# Teensy_Interface.net
KiCad netlist of a schematic drawn in Altium Designer
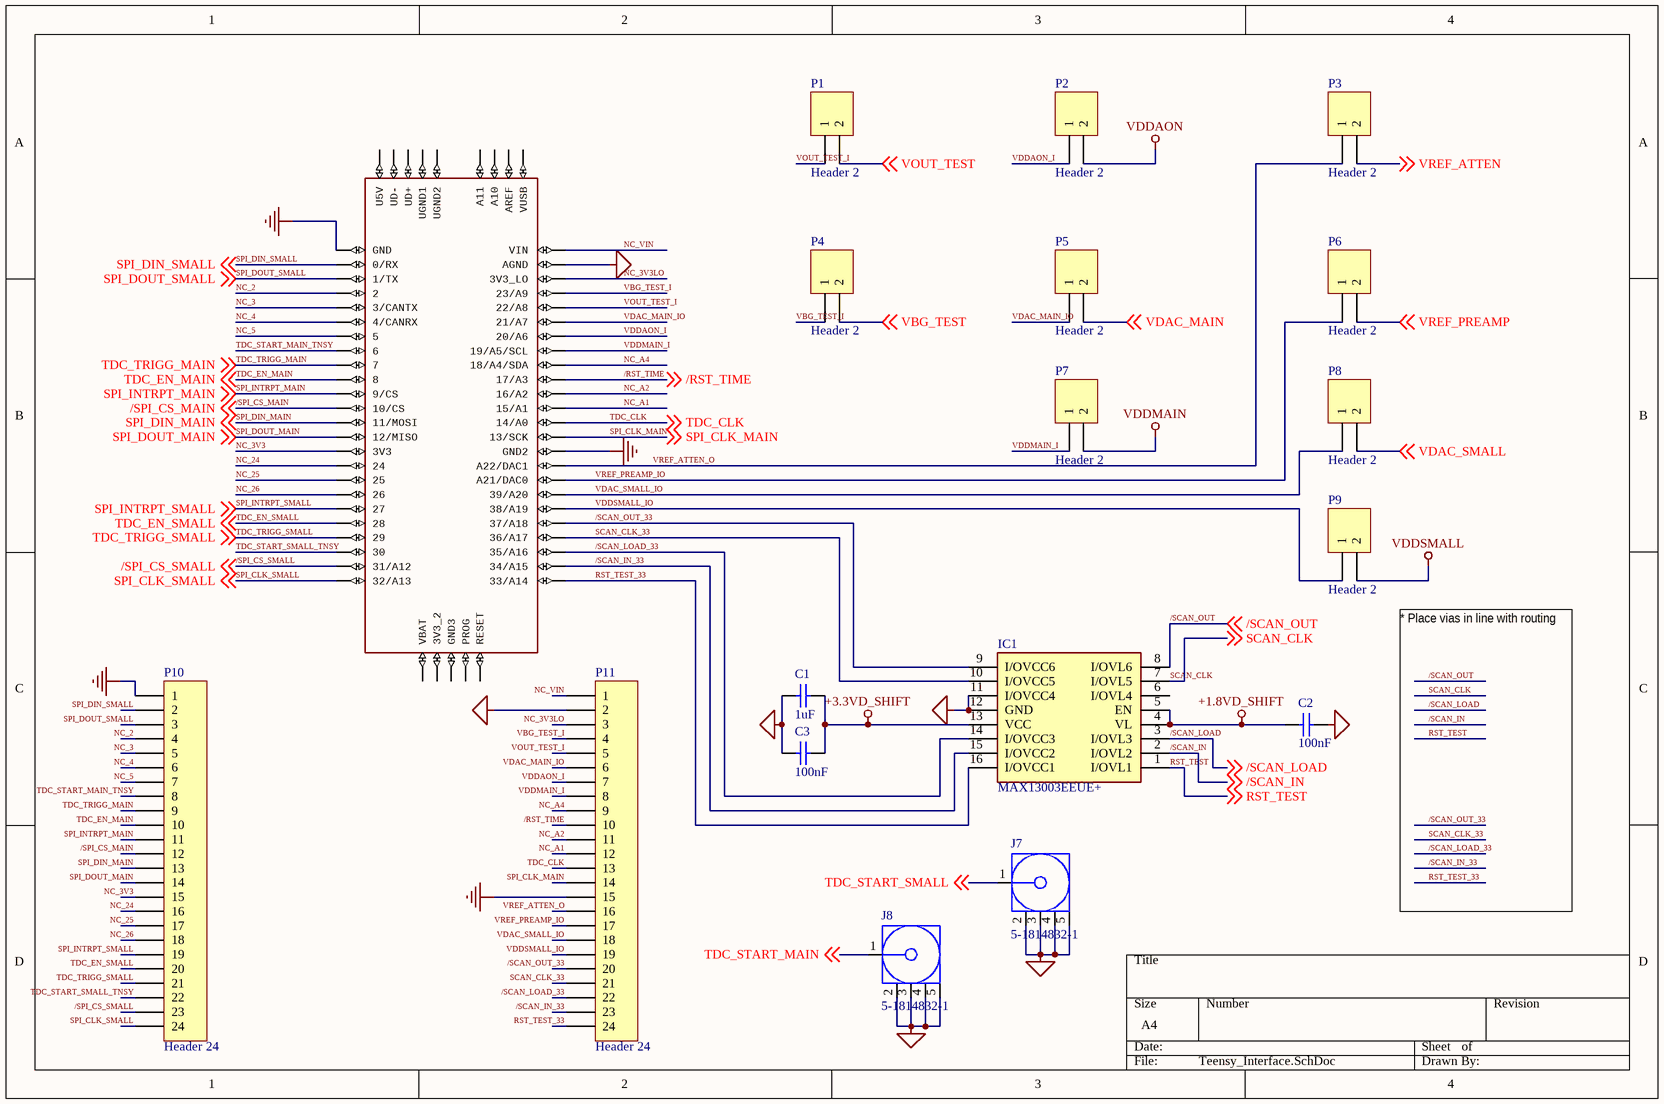
[diagram p0: Teensy_Interface.SchDoc]

(export (version "E")
  (design (tool "Eeschema 10.0.6"))
  (components
    (comp (ref "C1")
      (value "1uF")
      (footprint "CAPC1608X90X35ML10T15")
      (description "0603")
      (fields (field (name "MANUFACTURER") "Murata"))
      (libsource (lib "Altium Content Vault") (part "CAP-NP-2"))
    )
    (comp (ref "C2")
      (value "100nF")
      (footprint "CAPC1608X90X35ML10T15")
      (description "0603")
      (fields (field (name "MANUFACTURER") "Murata"))
      (libsource (lib "Altium Content Vault") (part "CAP-NP-2"))
    )
    (comp (ref "C3")
      (value "100nF")
      (footprint "CAPC1608X90X35ML10T15")
      (description "0603")
      (fields (field (name "MANUFACTURER") "Murata"))
      (libsource (lib "Altium Content Vault") (part "CAP-NP-2"))
    )
    (comp (ref "IC1")
      (value "MAX13003EEUE+")
      (footprint "SamacSys:SOP65P640X110-16N")
      (description "Integrated Circuit")
      (libsource (lib "*") (part "MAX13003EEUE+"))
    )
    (comp (ref "J7")
      (value "5-1814832-1")
      (footprint "TECO-5-1814832-1_V")
      (fields (field (name "MANUFACTURER") "TE Connectivity"))
      (libsource (lib "Altium Content Vault") (part "CN-S-4F-RF5"))
    )
    (comp (ref "J8")
      (value "5-1814832-1")
      (footprint "TECO-5-1814832-1_V")
      (fields (field (name "MANUFACTURER") "TE Connectivity"))
      (libsource (lib "Altium Content Vault") (part "CN-S-4F-RF5"))
    )
    (comp (ref "P1")
      (value "Header 2")
      (footprint "HDR1X2")
      (description "Header, 2-Pin")
      (fields (field (name "PUBLISHER") "Altium Limited"))
      (libsource (lib "Miscellaneous Connectors") (part "Header 2"))
    )
    (comp (ref "P2")
      (value "Header 2")
      (footprint "HDR1X2")
      (description "Header, 2-Pin")
      (fields (field (name "PUBLISHER") "Altium Limited"))
      (libsource (lib "Miscellaneous Connectors") (part "Header 2"))
    )
    (comp (ref "P3")
      (value "Header 2")
      (footprint "HDR1X2")
      (description "Header, 2-Pin")
      (fields (field (name "PUBLISHER") "Altium Limited"))
      (libsource (lib "Miscellaneous Connectors") (part "Header 2"))
    )
    (comp (ref "P4")
      (value "Header 2")
      (footprint "HDR1X2")
      (description "Header, 2-Pin")
      (fields (field (name "PUBLISHER") "Altium Limited"))
      (libsource (lib "Miscellaneous Connectors") (part "Header 2"))
    )
    (comp (ref "P5")
      (value "Header 2")
      (footprint "HDR1X2")
      (description "Header, 2-Pin")
      (fields (field (name "PUBLISHER") "Altium Limited"))
      (libsource (lib "Miscellaneous Connectors") (part "Header 2"))
    )
    (comp (ref "P6")
      (value "Header 2")
      (footprint "HDR1X2")
      (description "Header, 2-Pin")
      (fields (field (name "PUBLISHER") "Altium Limited"))
      (libsource (lib "Miscellaneous Connectors") (part "Header 2"))
    )
    (comp (ref "P7")
      (value "Header 2")
      (footprint "HDR1X2")
      (description "Header, 2-Pin")
      (fields (field (name "PUBLISHER") "Altium Limited"))
      (libsource (lib "Miscellaneous Connectors") (part "Header 2"))
    )
    (comp (ref "P8")
      (value "Header 2")
      (footprint "HDR1X2")
      (description "Header, 2-Pin")
      (fields (field (name "PUBLISHER") "Altium Limited"))
      (libsource (lib "Miscellaneous Connectors") (part "Header 2"))
    )
    (comp (ref "P9")
      (value "Header 2")
      (footprint "HDR1X2")
      (description "Header, 2-Pin")
      (fields (field (name "PUBLISHER") "Altium Limited"))
      (libsource (lib "Miscellaneous Connectors") (part "Header 2"))
    )
    (comp (ref "P10")
      (value "Header 24")
      (footprint "HDR1X24")
      (description "Header, 24-Pin")
      (fields (field (name "PUBLISHER") "Altium Limited"))
      (libsource (lib "Miscellaneous Connectors") (part "Header 24"))
    )
    (comp (ref "P11")
      (value "Header 24")
      (footprint "HDR1X24")
      (description "Header, 24-Pin")
      (fields (field (name "PUBLISHER") "Altium Limited"))
      (libsource (lib "Miscellaneous Connectors") (part "Header 24"))
    )
    (comp (ref "TEENSY1")
      (value "TEENSY_3.5/3.6")
      (footprint "TEENSY_3.5/3.6")
      (libsource (lib "Teensy356") (part "TEENSY_3.5/3.6"))
    )
  )
  (nets
    (net (code "1") (name "+1.8VD_SHIFT") (class "Default")
      (node (ref "C2") (pin "1") (pinfunction "1_1") (pintype "passive"))
      (node (ref "IC1") (pin "4") (pinfunction "VL_4") (pintype "passive"))
      (node (ref "IC1") (pin "5") (pinfunction "EN_5") (pintype "passive"))
    )
    (net (code "2") (name "+3.3VD_SHIFT") (class "Default")
      (node (ref "C1") (pin "2") (pinfunction "2_2") (pintype "passive"))
      (node (ref "C3") (pin "2") (pinfunction "2_2") (pintype "passive"))
      (node (ref "IC1") (pin "13") (pinfunction "VCC_13") (pintype "passive"))
    )
    (net (code "3") (name "/NC_2") (class "Default")
      (node (ref "P10") (pin "4") (pinfunction "4_4") (pintype "passive"))
      (node (ref "TEENSY1") (pin "2") (pinfunction "2_2") (pintype "bidirectional"))
    )
    (net (code "4") (name "/NC_3") (class "Default")
      (node (ref "P10") (pin "5") (pinfunction "5_5") (pintype "passive"))
      (node (ref "TEENSY1") (pin "3/CANTX") (pinfunction "3/CANTX_3/CANTX") (pintype "bidirectional"))
    )
    (net (code "5") (name "/NC_3V3") (class "Default")
      (node (ref "P10") (pin "15") (pinfunction "15_15") (pintype "passive"))
      (node (ref "TEENSY1") (pin "3V3") (pinfunction "3V3_3V3") (pintype "bidirectional"))
    )
    (net (code "6") (name "/NC_3V3LO") (class "Default")
      (node (ref "P11") (pin "3") (pinfunction "3_3") (pintype "passive"))
      (node (ref "TEENSY1") (pin "3V3_LO") (pinfunction "3V3_LO_3V3_LO") (pintype "bidirectional"))
    )
    (net (code "7") (name "/NC_4") (class "Default")
      (node (ref "P10") (pin "6") (pinfunction "6_6") (pintype "passive"))
      (node (ref "TEENSY1") (pin "4/CANRX") (pinfunction "4/CANRX_4/CANRX") (pintype "bidirectional"))
    )
    (net (code "8") (name "/NC_5") (class "Default")
      (node (ref "P10") (pin "7") (pinfunction "7_7") (pintype "passive"))
      (node (ref "TEENSY1") (pin "5") (pinfunction "5_5") (pintype "bidirectional"))
    )
    (net (code "9") (name "/NC_24") (class "Default")
      (node (ref "P10") (pin "16") (pinfunction "16_16") (pintype "passive"))
      (node (ref "TEENSY1") (pin "24") (pinfunction "24_24") (pintype "bidirectional"))
    )
    (net (code "10") (name "/NC_25") (class "Default")
      (node (ref "P10") (pin "17") (pinfunction "17_17") (pintype "passive"))
      (node (ref "TEENSY1") (pin "25") (pinfunction "25_25") (pintype "bidirectional"))
    )
    (net (code "11") (name "/NC_26") (class "Default")
      (node (ref "P10") (pin "18") (pinfunction "18_18") (pintype "passive"))
      (node (ref "TEENSY1") (pin "26") (pinfunction "26_26") (pintype "bidirectional"))
    )
    (net (code "12") (name "/NC_A1") (class "Default")
      (node (ref "P11") (pin "12") (pinfunction "12_12") (pintype "passive"))
      (node (ref "TEENSY1") (pin "15/A1") (pinfunction "15/A1_15/A1") (pintype "bidirectional"))
    )
    (net (code "13") (name "/NC_A2") (class "Default")
      (node (ref "P11") (pin "11") (pinfunction "11_11") (pintype "passive"))
      (node (ref "TEENSY1") (pin "16/A2") (pinfunction "16/A2_16/A2") (pintype "bidirectional"))
    )
    (net (code "14") (name "/NC_A4") (class "Default")
      (node (ref "P11") (pin "9") (pinfunction "9_9") (pintype "passive"))
      (node (ref "TEENSY1") (pin "18/A4/SDA") (pinfunction "18/A4/SDA_18/A4/SDA") (pintype "bidirectional"))
    )
    (net (code "15") (name "/NC_VIN") (class "Default")
      (node (ref "P11") (pin "1") (pinfunction "1_1") (pintype "passive"))
      (node (ref "TEENSY1") (pin "VIN") (pinfunction "VIN_VIN") (pintype "bidirectional"))
    )
    (net (code "16") (name "/RST_TEST_33") (class "Default")
      (node (ref "IC1") (pin "16") (pinfunction "I/OVCC1_16") (pintype "passive"))
      (node (ref "P11") (pin "24") (pinfunction "24_24") (pintype "passive"))
      (node (ref "TEENSY1") (pin "33/A14") (pinfunction "33/A14_33/A14") (pintype "bidirectional"))
    )
    (net (code "17") (name "/SCAN_CLK_33") (class "Default")
      (node (ref "IC1") (pin "10") (pinfunction "I/OVCC5_10") (pintype "passive"))
      (node (ref "P11") (pin "21") (pinfunction "21_21") (pintype "passive"))
      (node (ref "TEENSY1") (pin "36/A17") (pinfunction "36/A17_36/A17") (pintype "bidirectional"))
    )
    (net (code "18") (name "/TDC_START_MAIN_TNSY") (class "Default")
      (node (ref "P10") (pin "8") (pinfunction "8_8") (pintype "passive"))
      (node (ref "TEENSY1") (pin "6") (pinfunction "6_6") (pintype "bidirectional"))
    )
    (net (code "19") (name "/TDC_START_SMALL_TNSY") (class "Default")
      (node (ref "P10") (pin "22") (pinfunction "22_22") (pintype "passive"))
      (node (ref "TEENSY1") (pin "30") (pinfunction "30_30") (pintype "bidirectional"))
    )
    (net (code "20") (name "/VBG_TEST_I") (class "Default")
      (node (ref "P11") (pin "4") (pinfunction "4_4") (pintype "passive"))
      (node (ref "P4") (pin "1") (pinfunction "1_1") (pintype "passive"))
      (node (ref "TEENSY1") (pin "23/A9") (pinfunction "23/A9_23/A9") (pintype "bidirectional"))
    )
    (net (code "21") (name "/VDAC_MAIN_IO") (class "Default")
      (node (ref "P11") (pin "6") (pinfunction "6_6") (pintype "passive"))
      (node (ref "P5") (pin "1") (pinfunction "1_1") (pintype "passive"))
      (node (ref "TEENSY1") (pin "21/A7") (pinfunction "21/A7_21/A7") (pintype "bidirectional"))
    )
    (net (code "22") (name "/VDAC_SMALL_IO") (class "Default")
      (node (ref "P11") (pin "18") (pinfunction "18_18") (pintype "passive"))
      (node (ref "P8") (pin "1") (pinfunction "1_1") (pintype "passive"))
      (node (ref "TEENSY1") (pin "39/A20") (pinfunction "39/A20_39/A20") (pintype "bidirectional"))
    )
    (net (code "23") (name "/VDDAON_I") (class "Default")
      (node (ref "P11") (pin "7") (pinfunction "7_7") (pintype "passive"))
      (node (ref "P2") (pin "1") (pinfunction "1_1") (pintype "passive"))
      (node (ref "TEENSY1") (pin "20/A6") (pinfunction "20/A6_20/A6") (pintype "bidirectional"))
    )
    (net (code "24") (name "/VDDMAIN_I") (class "Default")
      (node (ref "P11") (pin "8") (pinfunction "8_8") (pintype "passive"))
      (node (ref "P7") (pin "1") (pinfunction "1_1") (pintype "passive"))
      (node (ref "TEENSY1") (pin "19/A5/SCL") (pinfunction "19/A5/SCL_19/A5/SCL") (pintype "bidirectional"))
    )
    (net (code "25") (name "/VDDSMALL_IO") (class "Default")
      (node (ref "P11") (pin "19") (pinfunction "19_19") (pintype "passive"))
      (node (ref "P9") (pin "1") (pinfunction "1_1") (pintype "passive"))
      (node (ref "TEENSY1") (pin "38/A19") (pinfunction "38/A19_38/A19") (pintype "bidirectional"))
    )
    (net (code "26") (name "/VOUT_TEST_I") (class "Default")
      (node (ref "P1") (pin "1") (pinfunction "1_1") (pintype "passive"))
      (node (ref "P11") (pin "5") (pinfunction "5_5") (pintype "passive"))
      (node (ref "TEENSY1") (pin "22/A8") (pinfunction "22/A8_22/A8") (pintype "bidirectional"))
    )
    (net (code "27") (name "/VREF_ATTEN_O") (class "Default")
      (node (ref "P11") (pin "16") (pinfunction "16_16") (pintype "passive"))
      (node (ref "P3") (pin "1") (pinfunction "1_1") (pintype "passive"))
      (node (ref "TEENSY1") (pin "A22/DAC1") (pinfunction "A22/DAC1_A22/DAC1") (pintype "bidirectional"))
    )
    (net (code "28") (name "/VREF_PREAMP_IO") (class "Default")
      (node (ref "P11") (pin "17") (pinfunction "17_17") (pintype "passive"))
      (node (ref "P6") (pin "1") (pinfunction "1_1") (pintype "passive"))
      (node (ref "TEENSY1") (pin "21/DAC0") (pinfunction "A21/DAC0_21/DAC0") (pintype "bidirectional"))
    )
    (net (code "29") (name "/{slash}SCAN_IN_33") (class "Default")
      (node (ref "IC1") (pin "15") (pinfunction "I/OVCC2_15") (pintype "passive"))
      (node (ref "P11") (pin "23") (pinfunction "23_23") (pintype "passive"))
      (node (ref "TEENSY1") (pin "34/A15") (pinfunction "34/A15_34/A15") (pintype "bidirectional"))
    )
    (net (code "30") (name "/{slash}SCAN_LOAD_33") (class "Default")
      (node (ref "IC1") (pin "14") (pinfunction "I/OVCC3_14") (pintype "passive"))
      (node (ref "P11") (pin "22") (pinfunction "22_22") (pintype "passive"))
      (node (ref "TEENSY1") (pin "35/A16") (pinfunction "35/A16_35/A16") (pintype "bidirectional"))
    )
    (net (code "31") (name "/{slash}SCAN_OUT_33") (class "Default")
      (node (ref "IC1") (pin "9") (pinfunction "I/OVCC6_9") (pintype "passive"))
      (node (ref "P11") (pin "20") (pinfunction "20_20") (pintype "passive"))
      (node (ref "TEENSY1") (pin "37/A18") (pinfunction "37/A18_37/A18") (pintype "bidirectional"))
    )
    (net (code "32") (name "GND") (class "Default")
      (node (ref "C1") (pin "1") (pinfunction "1_1") (pintype "passive"))
      (node (ref "C2") (pin "2") (pinfunction "2_2") (pintype "passive"))
      (node (ref "C3") (pin "1") (pinfunction "1_1") (pintype "passive"))
      (node (ref "IC1") (pin "11") (pinfunction "I/OVCC4_11") (pintype "passive"))
      (node (ref "IC1") (pin "12") (pinfunction "GND_12") (pintype "passive"))
      (node (ref "J7") (pin "2") (pinfunction "2_2") (pintype "passive"))
      (node (ref "J7") (pin "3") (pinfunction "3_3") (pintype "passive"))
      (node (ref "J7") (pin "4") (pinfunction "4_4") (pintype "passive"))
      (node (ref "J7") (pin "5") (pinfunction "5_5") (pintype "passive"))
      (node (ref "J8") (pin "2") (pinfunction "2_2") (pintype "passive"))
      (node (ref "J8") (pin "3") (pinfunction "3_3") (pintype "passive"))
      (node (ref "J8") (pin "4") (pinfunction "4_4") (pintype "passive"))
      (node (ref "J8") (pin "5") (pinfunction "5_5") (pintype "passive"))
      (node (ref "P10") (pin "1") (pinfunction "1_1") (pintype "passive"))
      (node (ref "P11") (pin "15") (pinfunction "15_15") (pintype "passive"))
      (node (ref "P11") (pin "2") (pinfunction "2_2") (pintype "passive"))
      (node (ref "TEENSY1") (pin "AGND") (pinfunction "AGND_AGND") (pintype "bidirectional"))
      (node (ref "TEENSY1") (pin "GND") (pinfunction "GND_GND") (pintype "bidirectional"))
      (node (ref "TEENSY1") (pin "GND2") (pinfunction "GND2_GND2") (pintype "bidirectional"))
    )
    (net (code "33") (name "RST_TEST") (class "Default")
      (node (ref "IC1") (pin "1") (pinfunction "I/OVL1_1") (pintype "passive"))
    )
    (net (code "34") (name "SCAN_CLK") (class "Default")
      (node (ref "IC1") (pin "7") (pinfunction "I/OVL5_7") (pintype "passive"))
    )
    (net (code "35") (name "SPI_CLK_MAIN") (class "Default")
      (node (ref "P11") (pin "14") (pinfunction "14_14") (pintype "passive"))
      (node (ref "TEENSY1") (pin "13/SCK") (pinfunction "13/SCK_13/SCK") (pintype "bidirectional"))
    )
    (net (code "36") (name "SPI_CLK_SMALL") (class "Default")
      (node (ref "P10") (pin "24") (pinfunction "24_24") (pintype "passive"))
      (node (ref "TEENSY1") (pin "32/A13") (pinfunction "32/A13_32/A13") (pintype "bidirectional"))
    )
    (net (code "37") (name "SPI_DIN_MAIN") (class "Default")
      (node (ref "P10") (pin "13") (pinfunction "13_13") (pintype "passive"))
      (node (ref "TEENSY1") (pin "11/MOSI") (pinfunction "11/MOSI_11/MOSI") (pintype "bidirectional"))
    )
    (net (code "38") (name "SPI_DIN_SMALL") (class "Default")
      (node (ref "P10") (pin "2") (pinfunction "2_2") (pintype "passive"))
      (node (ref "TEENSY1") (pin "0/RX") (pinfunction "0/RX_0/RX") (pintype "bidirectional"))
    )
    (net (code "39") (name "SPI_DOUT_MAIN") (class "Default")
      (node (ref "P10") (pin "14") (pinfunction "14_14") (pintype "passive"))
      (node (ref "TEENSY1") (pin "12/MISO") (pinfunction "12/MISO_12/MISO") (pintype "bidirectional"))
    )
    (net (code "40") (name "SPI_DOUT_SMALL") (class "Default")
      (node (ref "P10") (pin "3") (pinfunction "3_3") (pintype "passive"))
      (node (ref "TEENSY1") (pin "1/TX") (pinfunction "1/TX_1/TX") (pintype "bidirectional"))
    )
    (net (code "41") (name "SPI_INTRPT_MAIN") (class "Default")
      (node (ref "P10") (pin "11") (pinfunction "11_11") (pintype "passive"))
      (node (ref "TEENSY1") (pin "9/CS") (pinfunction "9/CS_9/CS") (pintype "bidirectional"))
    )
    (net (code "42") (name "SPI_INTRPT_SMALL") (class "Default")
      (node (ref "P10") (pin "19") (pinfunction "19_19") (pintype "passive"))
      (node (ref "TEENSY1") (pin "27") (pinfunction "27_27") (pintype "bidirectional"))
    )
    (net (code "43") (name "TDC_CLK") (class "Default")
      (node (ref "P11") (pin "13") (pinfunction "13_13") (pintype "passive"))
      (node (ref "TEENSY1") (pin "14/A0") (pinfunction "14/A0_14/A0") (pintype "bidirectional"))
    )
    (net (code "44") (name "TDC_EN_MAIN") (class "Default")
      (node (ref "P10") (pin "10") (pinfunction "10_10") (pintype "passive"))
      (node (ref "TEENSY1") (pin "8") (pinfunction "8_8") (pintype "bidirectional"))
    )
    (net (code "45") (name "TDC_EN_SMALL") (class "Default")
      (node (ref "P10") (pin "20") (pinfunction "20_20") (pintype "passive"))
      (node (ref "TEENSY1") (pin "28") (pinfunction "28_28") (pintype "bidirectional"))
    )
    (net (code "46") (name "TDC_START_MAIN") (class "Default")
      (node (ref "J8") (pin "1") (pinfunction "1_1") (pintype "passive"))
    )
    (net (code "47") (name "TDC_START_SMALL") (class "Default")
      (node (ref "J7") (pin "1") (pinfunction "1_1") (pintype "passive"))
    )
    (net (code "48") (name "TDC_TRIGG_MAIN") (class "Default")
      (node (ref "P10") (pin "9") (pinfunction "9_9") (pintype "passive"))
      (node (ref "TEENSY1") (pin "7") (pinfunction "7_7") (pintype "bidirectional"))
    )
    (net (code "49") (name "TDC_TRIGG_SMALL") (class "Default")
      (node (ref "P10") (pin "21") (pinfunction "21_21") (pintype "passive"))
      (node (ref "TEENSY1") (pin "29") (pinfunction "29_29") (pintype "bidirectional"))
    )
    (net (code "50") (name "VBG_TEST") (class "Default")
      (node (ref "P4") (pin "2") (pinfunction "2_2") (pintype "passive"))
    )
    (net (code "51") (name "VDAC_MAIN") (class "Default")
      (node (ref "P5") (pin "2") (pinfunction "2_2") (pintype "passive"))
    )
    (net (code "52") (name "VDAC_SMALL") (class "Default")
      (node (ref "P8") (pin "2") (pinfunction "2_2") (pintype "passive"))
    )
    (net (code "53") (name "VDDAON") (class "Default")
      (node (ref "P2") (pin "2") (pinfunction "2_2") (pintype "passive"))
    )
    (net (code "54") (name "VDDMAIN") (class "Default")
      (node (ref "P7") (pin "2") (pinfunction "2_2") (pintype "passive"))
    )
    (net (code "55") (name "VDDSMALL") (class "Default")
      (node (ref "P9") (pin "2") (pinfunction "2_2") (pintype "passive"))
    )
    (net (code "56") (name "VOUT_TEST") (class "Default")
      (node (ref "P1") (pin "2") (pinfunction "2_2") (pintype "passive"))
    )
    (net (code "57") (name "VREF_ATTEN") (class "Default")
      (node (ref "P3") (pin "2") (pinfunction "2_2") (pintype "passive"))
    )
    (net (code "58") (name "VREF_PREAMP") (class "Default")
      (node (ref "P6") (pin "2") (pinfunction "2_2") (pintype "passive"))
    )
    (net (code "59") (name "unconnected-(IC1-I{slash}OVL4-Pad6)") (class "Default")
      (node (ref "IC1") (pin "6") (pinfunction "I/OVL4_6") (pintype "passive"))
    )
    (net (code "60") (name "unconnected-(TEENSY1-Pad3V3_2)") (class "Default")
      (node (ref "TEENSY1") (pin "3V3_2") (pinfunction "3V3_2_3V3_2") (pintype "bidirectional"))
    )
    (net (code "61") (name "unconnected-(TEENSY1-PadA10)") (class "Default")
      (node (ref "TEENSY1") (pin "A10") (pinfunction "A10_A10") (pintype "bidirectional"))
    )
    (net (code "62") (name "unconnected-(TEENSY1-PadA11)") (class "Default")
      (node (ref "TEENSY1") (pin "A11") (pinfunction "A11_A11") (pintype "bidirectional"))
    )
    (net (code "63") (name "unconnected-(TEENSY1-PadAREF)") (class "Default")
      (node (ref "TEENSY1") (pin "AREF") (pinfunction "AREF_AREF") (pintype "bidirectional"))
    )
    (net (code "64") (name "unconnected-(TEENSY1-PadGND3)") (class "Default")
      (node (ref "TEENSY1") (pin "GND3") (pinfunction "GND3_GND3") (pintype "bidirectional"))
    )
    (net (code "65") (name "unconnected-(TEENSY1-PadPROG)") (class "Default")
      (node (ref "TEENSY1") (pin "PROG") (pinfunction "PROG_PROG") (pintype "bidirectional"))
    )
    (net (code "66") (name "unconnected-(TEENSY1-PadRESET)") (class "Default")
      (node (ref "TEENSY1") (pin "RESET") (pinfunction "RESET_RESET") (pintype "bidirectional"))
    )
    (net (code "67") (name "unconnected-(TEENSY1-PadU5V)") (class "Default")
      (node (ref "TEENSY1") (pin "U5V") (pinfunction "U5V_U5V") (pintype "bidirectional"))
    )
    (net (code "68") (name "unconnected-(TEENSY1-PadUD+)") (class "Default")
      (node (ref "TEENSY1") (pin "UD+") (pinfunction "UD+_UD+") (pintype "bidirectional"))
    )
    (net (code "69") (name "unconnected-(TEENSY1-PadUD-)") (class "Default")
      (node (ref "TEENSY1") (pin "UD-") (pinfunction "UD-_UD-") (pintype "bidirectional"))
    )
    (net (code "70") (name "unconnected-(TEENSY1-PadUGND1)") (class "Default")
      (node (ref "TEENSY1") (pin "UGND1") (pinfunction "UGND1_UGND1") (pintype "bidirectional"))
    )
    (net (code "71") (name "unconnected-(TEENSY1-PadUGND2)") (class "Default")
      (node (ref "TEENSY1") (pin "UGND2") (pinfunction "UGND2_UGND2") (pintype "bidirectional"))
    )
    (net (code "72") (name "unconnected-(TEENSY1-PadVBAT)") (class "Default")
      (node (ref "TEENSY1") (pin "VBAT") (pinfunction "VBAT_VBAT") (pintype "bidirectional"))
    )
    (net (code "73") (name "unconnected-(TEENSY1-PadVUSB)") (class "Default")
      (node (ref "TEENSY1") (pin "VUSB") (pinfunction "VUSB_VUSB") (pintype "bidirectional"))
    )
    (net (code "74") (name "{slash}RST_TIME") (class "Default")
      (node (ref "P11") (pin "10") (pinfunction "10_10") (pintype "passive"))
      (node (ref "TEENSY1") (pin "17/A3") (pinfunction "17/A3_17/A3") (pintype "bidirectional"))
    )
    (net (code "75") (name "{slash}SCAN_IN") (class "Default")
      (node (ref "IC1") (pin "2") (pinfunction "I/OVL2_2") (pintype "passive"))
    )
    (net (code "76") (name "{slash}SCAN_LOAD") (class "Default")
      (node (ref "IC1") (pin "3") (pinfunction "I/OVL3_3") (pintype "passive"))
    )
    (net (code "77") (name "{slash}SCAN_OUT") (class "Default")
      (node (ref "IC1") (pin "8") (pinfunction "I/OVL6_8") (pintype "passive"))
    )
    (net (code "78") (name "{slash}SPI_CS_MAIN") (class "Default")
      (node (ref "P10") (pin "12") (pinfunction "12_12") (pintype "passive"))
      (node (ref "TEENSY1") (pin "10/CS") (pinfunction "10/CS_10/CS") (pintype "bidirectional"))
    )
    (net (code "79") (name "{slash}SPI_CS_SMALL") (class "Default")
      (node (ref "P10") (pin "23") (pinfunction "23_23") (pintype "passive"))
      (node (ref "TEENSY1") (pin "31/A12") (pinfunction "31/A12_31/A12") (pintype "bidirectional"))
    )
  )
)
